# gonzoCam.net
KiCad netlist of a schematic drawn in EAGLE
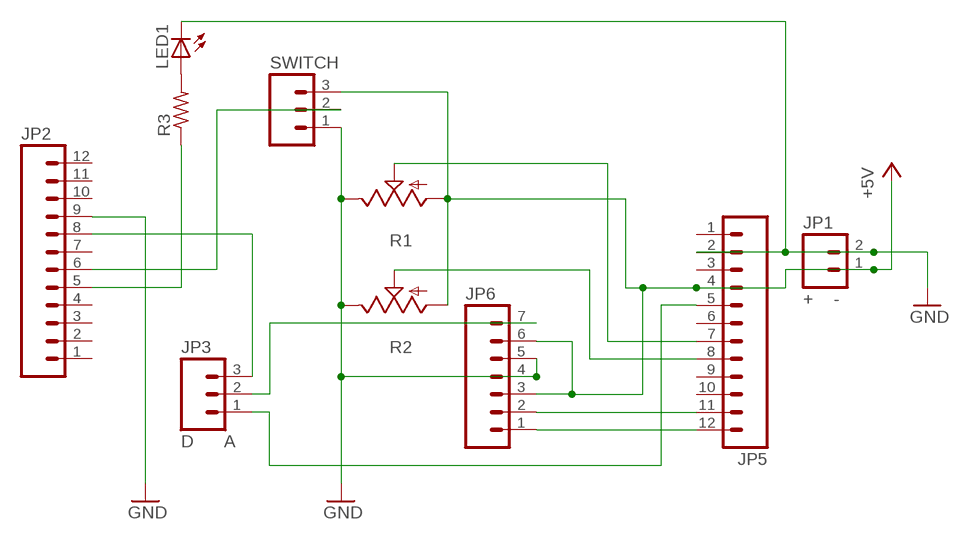
[diagram p0: schematic, sheet 1]

(export (version "E")
  (design (tool "Eeschema 10.0.6"))
  (components
    (comp (ref "JP1")
      (value "+ -")
      (footprint "eagle-import:1X02")
      (libsource (lib "eagle-import") (part "M02PTH"))
    )
    (comp (ref "JP2")
      (value "M12PTH")
      (footprint "eagle-import:1X12")
      (libsource (lib "eagle-import") (part "M12PTH"))
    )
    (comp (ref "JP3")
      (value "D A")
      (footprint "eagle-import:1X03")
      (libsource (lib "eagle-import") (part "M03PTH"))
    )
    (comp (ref "JP5")
      (value "M12PTH")
      (footprint "eagle-import:1X12")
      (libsource (lib "eagle-import") (part "M12PTH"))
    )
    (comp (ref "JP6")
      (value "M07")
      (footprint "eagle-import:1X07")
      (libsource (lib "eagle-import") (part "M07"))
    )
    (comp (ref "LED1")
      (value "LED3MM")
      (footprint "eagle-import:LED3MM")
      (libsource (lib "eagle-import") (part "LED3MM"))
    )
    (comp (ref "R1")
      (value "TRIM_US-CA6V")
      (footprint "eagle-import:CA6V")
      (libsource (lib "eagle-import") (part "TRIM_US-CA6V"))
    )
    (comp (ref "R2")
      (value "TRIM_US-CA6V")
      (footprint "eagle-import:CA6V")
      (libsource (lib "eagle-import") (part "TRIM_US-CA6V"))
    )
    (comp (ref "R3")
      (value "R-US_0204/5")
      (footprint "eagle-import:0204_5")
      (libsource (lib "eagle-import") (part "R-US_0204/5"))
    )
    (comp (ref "SWITCH")
      (value "M03PTH")
      (footprint "eagle-import:1X03")
      (libsource (lib "eagle-import") (part "M03PTH"))
    )
  )
  (nets
    (net (code "1") (name "+5V") (class "Default")
      (node (ref "JP1") (pin "1") (pinfunction "1_1") (pintype "passive"))
      (node (ref "JP5") (pin "4") (pinfunction "4_4") (pintype "passive"))
      (node (ref "JP6") (pin "3") (pinfunction "3_3") (pintype "passive"))
      (node (ref "JP6") (pin "6") (pinfunction "6_6") (pintype "passive"))
      (node (ref "R1") (pin "A") (pinfunction "A_A") (pintype "passive"))
      (node (ref "R2") (pin "A") (pinfunction "A_A") (pintype "passive"))
      (node (ref "SWITCH") (pin "3") (pinfunction "3_3") (pintype "passive"))
    )
    (net (code "2") (name "GND") (class "Default")
      (node (ref "JP1") (pin "2") (pinfunction "2_2") (pintype "passive"))
      (node (ref "JP2") (pin "9") (pinfunction "9_9") (pintype "passive"))
      (node (ref "JP5") (pin "2") (pinfunction "2_2") (pintype "passive"))
      (node (ref "JP6") (pin "4") (pinfunction "4_4") (pintype "passive"))
      (node (ref "JP6") (pin "5") (pinfunction "5_5") (pintype "passive"))
      (node (ref "LED1") (pin "K") (pinfunction "C_K") (pintype "passive"))
      (node (ref "R1") (pin "E") (pinfunction "E_E") (pintype "passive"))
      (node (ref "R2") (pin "E") (pinfunction "E_E") (pintype "passive"))
      (node (ref "SWITCH") (pin "1") (pinfunction "1_1") (pintype "passive"))
    )
    (net (code "3") (name "Net-(JP2-Pad5)") (class "Default")
      (node (ref "JP2") (pin "5") (pinfunction "5_5") (pintype "passive"))
      (node (ref "R3") (pin "1") (pinfunction "1_1") (pintype "passive"))
    )
    (net (code "4") (name "Net-(JP2-Pad6)") (class "Default")
      (node (ref "JP2") (pin "6") (pinfunction "6_6") (pintype "passive"))
      (node (ref "SWITCH") (pin "2") (pinfunction "2_2") (pintype "passive"))
    )
    (net (code "5") (name "Net-(JP2-Pad8)") (class "Default")
      (node (ref "JP2") (pin "8") (pinfunction "8_8") (pintype "passive"))
      (node (ref "JP3") (pin "3") (pinfunction "3_3") (pintype "passive"))
    )
    (net (code "6") (name "Net-(JP3-Pad1)") (class "Default")
      (node (ref "JP3") (pin "1") (pinfunction "1_1") (pintype "passive"))
      (node (ref "JP5") (pin "5") (pinfunction "5_5") (pintype "passive"))
    )
    (net (code "7") (name "Net-(JP3-Pad2)") (class "Default")
      (node (ref "JP3") (pin "2") (pinfunction "2_2") (pintype "passive"))
      (node (ref "JP6") (pin "7") (pinfunction "7_7") (pintype "passive"))
    )
    (net (code "8") (name "Net-(JP5-Pad7)") (class "Default")
      (node (ref "JP5") (pin "7") (pinfunction "7_7") (pintype "passive"))
      (node (ref "R1") (pin "S") (pinfunction "S_S") (pintype "passive"))
    )
    (net (code "9") (name "Net-(JP5-Pad8)") (class "Default")
      (node (ref "JP5") (pin "8") (pinfunction "8_8") (pintype "passive"))
      (node (ref "R2") (pin "S") (pinfunction "S_S") (pintype "passive"))
    )
    (net (code "10") (name "Net-(JP5-Pad11)") (class "Default")
      (node (ref "JP5") (pin "11") (pinfunction "11_11") (pintype "passive"))
      (node (ref "JP6") (pin "2") (pinfunction "2_2") (pintype "passive"))
    )
    (net (code "11") (name "Net-(JP5-Pad12)") (class "Default")
      (node (ref "JP5") (pin "12") (pinfunction "12_12") (pintype "passive"))
      (node (ref "JP6") (pin "1") (pinfunction "1_1") (pintype "passive"))
    )
    (net (code "12") (name "Net-(LED1-PadA)") (class "Default")
      (node (ref "LED1") (pin "A") (pinfunction "A_A") (pintype "passive"))
      (node (ref "R3") (pin "2") (pinfunction "2_2") (pintype "passive"))
    )
    (net (code "13") (name "unconnected-(JP2-Pad1)") (class "Default")
      (node (ref "JP2") (pin "1") (pinfunction "1_1") (pintype "passive"))
    )
    (net (code "14") (name "unconnected-(JP2-Pad2)") (class "Default")
      (node (ref "JP2") (pin "2") (pinfunction "2_2") (pintype "passive"))
    )
    (net (code "15") (name "unconnected-(JP2-Pad3)") (class "Default")
      (node (ref "JP2") (pin "3") (pinfunction "3_3") (pintype "passive"))
    )
    (net (code "16") (name "unconnected-(JP2-Pad4)") (class "Default")
      (node (ref "JP2") (pin "4") (pinfunction "4_4") (pintype "passive"))
    )
    (net (code "17") (name "unconnected-(JP2-Pad7)") (class "Default")
      (node (ref "JP2") (pin "7") (pinfunction "7_7") (pintype "passive"))
    )
    (net (code "18") (name "unconnected-(JP2-Pad10)") (class "Default")
      (node (ref "JP2") (pin "10") (pinfunction "10_10") (pintype "passive"))
    )
    (net (code "19") (name "unconnected-(JP2-Pad11)") (class "Default")
      (node (ref "JP2") (pin "11") (pinfunction "11_11") (pintype "passive"))
    )
    (net (code "20") (name "unconnected-(JP2-Pad12)") (class "Default")
      (node (ref "JP2") (pin "12") (pinfunction "12_12") (pintype "passive"))
    )
    (net (code "21") (name "unconnected-(JP5-Pad1)") (class "Default")
      (node (ref "JP5") (pin "1") (pinfunction "1_1") (pintype "passive"))
    )
    (net (code "22") (name "unconnected-(JP5-Pad3)") (class "Default")
      (node (ref "JP5") (pin "3") (pinfunction "3_3") (pintype "passive"))
    )
    (net (code "23") (name "unconnected-(JP5-Pad6)") (class "Default")
      (node (ref "JP5") (pin "6") (pinfunction "6_6") (pintype "passive"))
    )
    (net (code "24") (name "unconnected-(JP5-Pad9)") (class "Default")
      (node (ref "JP5") (pin "9") (pinfunction "9_9") (pintype "passive"))
    )
    (net (code "25") (name "unconnected-(JP5-Pad10)") (class "Default")
      (node (ref "JP5") (pin "10") (pinfunction "10_10") (pintype "passive"))
    )
  )
)
